# HANDS_FREE_MotorDrive_V2.net
KiCad netlist of a schematic drawn in Altium Designer
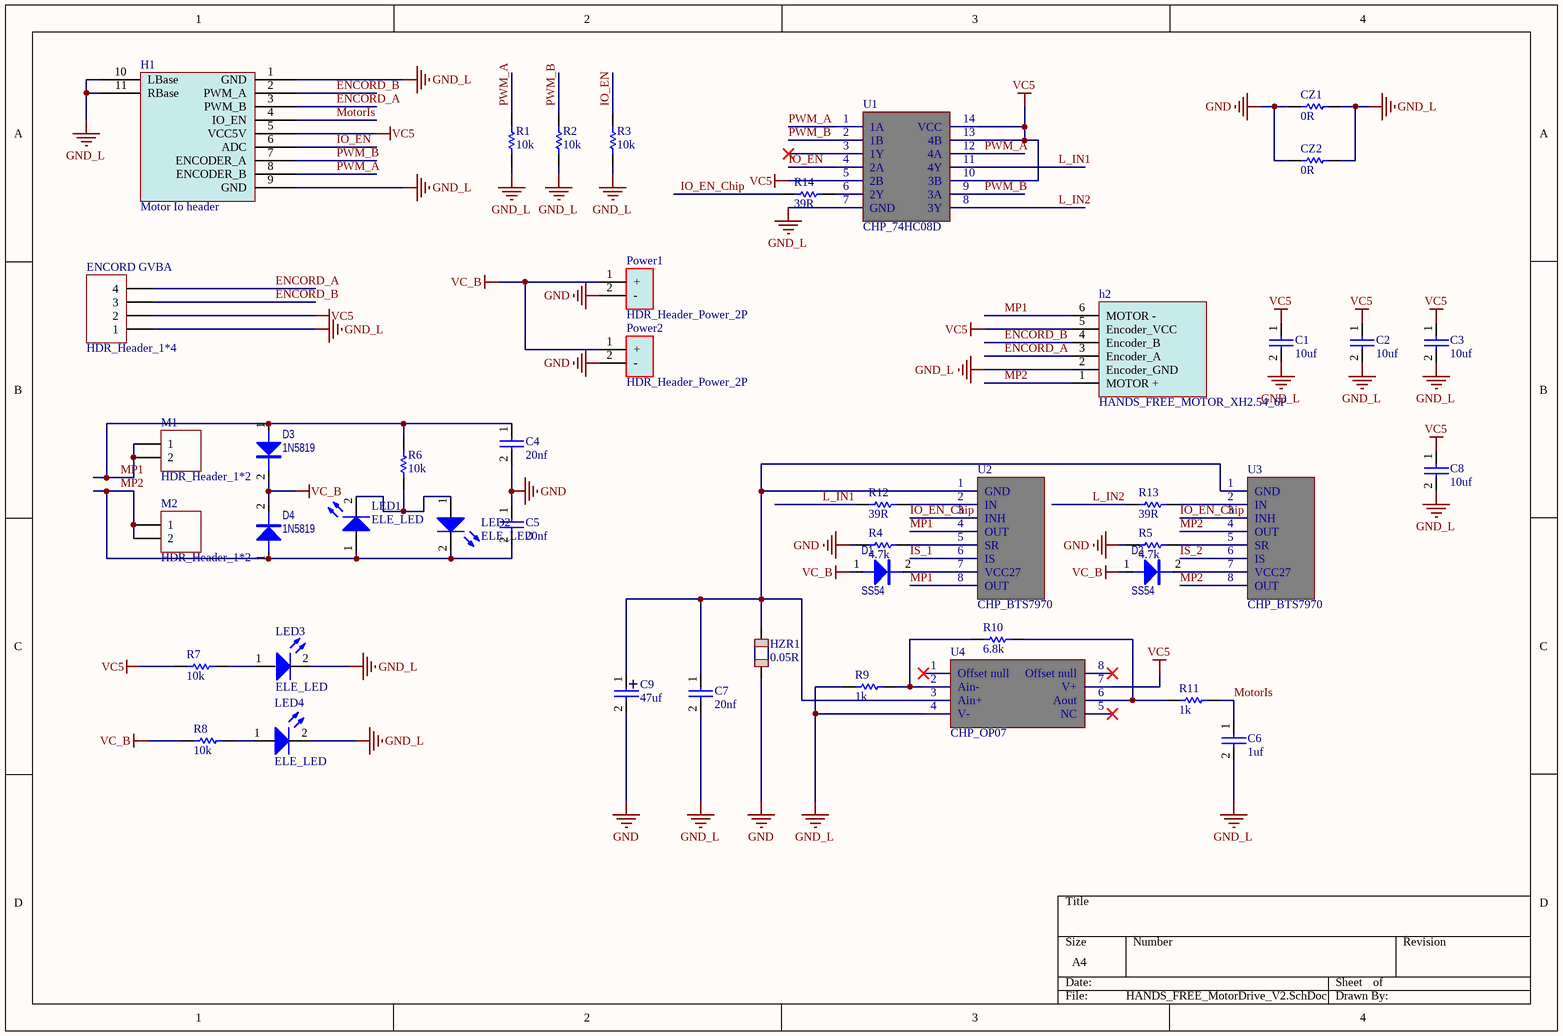
[diagram p0: HANDS_FREE_MotorDrive_V2.SchDoc]

(export (version "E")
  (design (tool "Eeschema 10.0.6"))
  (components
    (comp (ref "C1")
      (value "10uf")
      (footprint "ELE_0603_P")
      (description "电容")
      (libsource (lib "Hands_free") (part "ELE_Cap"))
    )
    (comp (ref "C2")
      (value "10uf")
      (footprint "ELE_0603_P")
      (description "电容")
      (libsource (lib "Hands_free") (part "ELE_Cap"))
    )
    (comp (ref "C3")
      (value "10uf")
      (footprint "ELE_0603_P")
      (description "电容")
      (libsource (lib "Hands_free") (part "ELE_Cap"))
    )
    (comp (ref "C4")
      (value "20nf")
      (footprint "ELE_0603_P")
      (description "电容")
      (libsource (lib "Hands_free") (part "ELE_Cap"))
    )
    (comp (ref "C5")
      (value "20nf")
      (footprint "ELE_0603_P")
      (description "电容")
      (libsource (lib "Hands_free") (part "ELE_Cap"))
    )
    (comp (ref "C6")
      (value "1uf")
      (footprint "ELE_0603_P")
      (description "电容")
      (libsource (lib "Hands_free") (part "ELE_Cap"))
    )
    (comp (ref "C7")
      (value "20nf")
      (footprint "ELE_0603_P")
      (description "电容")
      (libsource (lib "Hands_free") (part "ELE_Cap"))
    )
    (comp (ref "C8")
      (value "10uf")
      (footprint "ELE_0603_P")
      (description "电容")
      (libsource (lib "Hands_free") (part "ELE_Cap"))
    )
    (comp (ref "C9")
      (value "47uf")
      (footprint "ELE_CAP_DV_5*X")
      (description "贴片 极性电容 0603")
      (libsource (lib "Hands_free") (part "ELE_Cap_Pole"))
    )
    (comp (ref "CZ1")
      (value "0R")
      (footprint "ELE_0603_P")
      (description "贴片 电阻")
      (libsource (lib "Hands_free") (part "ELE_RES"))
    )
    (comp (ref "CZ2")
      (value "0R")
      (footprint "ELE_0603_P")
      (description "贴片 电阻")
      (libsource (lib "Hands_free") (part "ELE_RES"))
    )
    (comp (ref "D1")
      (value "SS54")
      (footprint "ELE_D1206")
      (description "贴片 二极管 1206")
      (libsource (lib "Hands_free") (part "ELE_Diode"))
    )
    (comp (ref "D2")
      (value "SS54")
      (footprint "ELE_D1206")
      (description "贴片 二极管 1206")
      (libsource (lib "Hands_free") (part "ELE_Diode"))
    )
    (comp (ref "D3")
      (value "1N5819")
      (footprint "ELE_SOD-323")
      (description "贴片 二极管 SOD323")
      (libsource (lib "Hands_free") (part "ELE_Standard_Diode_SOD323"))
    )
    (comp (ref "D4")
      (value "1N5819")
      (footprint "ELE_SOD-323")
      (description "贴片 二极管 SOD323")
      (libsource (lib "Hands_free") (part "ELE_Standard_Diode_SOD323"))
    )
    (comp (ref "ENCORD GVBA")
      (value "HDR_Header_1*4")
      (footprint "HDR_Header_2.54_PH_1*4")
      (fields (field (name "PUBLISHER") "Altium Limited"))
      (libsource (lib "Hands_free") (part "HDR_Header_1*4"))
    )
    (comp (ref "H1")
      (value "Motor Io header")
      (footprint "HDR_Molex_PH_1.25_9P")
      (description "卧贴 molex 1.25间距 9P接口")
      (libsource (lib "Hands_free") (part "HANDS_FREE_MOTOR"))
    )
    (comp (ref "h2")
      (value "HANDS_FREE_MOTOR_XH2.54_6P")
      (footprint "HDR_Header_XH2.54_DH_1*6")
      (description "直插 XH2.54 卧贴 6P")
      (libsource (lib "Hands_free") (part "HANDS_FREE_MOTOR_XH2.54_6P"))
    )
    (comp (ref "HZR1")
      (value "0.05R")
      (footprint "ELE_2512_P")
      (description "2512合金电阻 2W")
      (libsource (lib "Hands_free") (part "ELE_RES_HZR"))
    )
    (comp (ref "LED1")
      (value "ELE_LED")
      (footprint "ELE_0603极性_P")
      (description "发光二极管 0603")
      (fields (field (name "PUBLISHER") "Altium Limited"))
      (libsource (lib "Hands_free") (part "ELE_LED"))
    )
    (comp (ref "LED2")
      (value "ELE_LED")
      (footprint "ELE_0603极性_P")
      (description "发光二极管 0603")
      (fields (field (name "PUBLISHER") "Altium Limited"))
      (libsource (lib "Hands_free") (part "ELE_LED"))
    )
    (comp (ref "LED3")
      (value "ELE_LED")
      (footprint "ELE_0603极性_P")
      (description "发光二极管 0603")
      (fields (field (name "PUBLISHER") "Altium Limited"))
      (libsource (lib "Hands_free") (part "ELE_LED"))
    )
    (comp (ref "LED4")
      (value "ELE_LED")
      (footprint "ELE_0603极性_P")
      (description "发光二极管 0603")
      (fields (field (name "PUBLISHER") "Altium Limited"))
      (libsource (lib "Hands_free") (part "ELE_LED"))
    )
    (comp (ref "M1")
      (value "HDR_Header_1*2")
      (footprint "HDR_H_PH_2P")
      (fields (field (name "PUBLISHER") "Altium Limited"))
      (libsource (lib "Hands_free") (part "HDR_Header_1*2"))
    )
    (comp (ref "M2")
      (value "HDR_Header_1*2")
      (footprint "HDR_H_PH_2P")
      (fields (field (name "PUBLISHER") "Altium Limited"))
      (libsource (lib "Hands_free") (part "HDR_Header_1*2"))
    )
    (comp (ref "Power1")
      (value "HDR_Header_Power_2P")
      (footprint "HDR_MOLEX_POWER5557_DH_2P")
      (libsource (lib "Hands_free") (part "HDR_Header_Power_2P"))
    )
    (comp (ref "Power2")
      (value "HDR_Header_Power_2P")
      (footprint "HDR_MOLEX_POWER5557_DH_2P")
      (libsource (lib "Hands_free") (part "HDR_Header_Power_2P"))
    )
    (comp (ref "R1")
      (value "10k")
      (footprint "ELE_0603_P")
      (description "贴片 电阻")
      (libsource (lib "Hands_free") (part "ELE_RES"))
    )
    (comp (ref "R2")
      (value "10k")
      (footprint "ELE_0603_P")
      (description "贴片 电阻")
      (libsource (lib "Hands_free") (part "ELE_RES"))
    )
    (comp (ref "R3")
      (value "10k")
      (footprint "ELE_0603_P")
      (description "贴片 电阻")
      (libsource (lib "Hands_free") (part "ELE_RES"))
    )
    (comp (ref "R4")
      (value "4.7k")
      (footprint "ELE_0603_P")
      (description "贴片 电阻")
      (libsource (lib "Hands_free") (part "ELE_RES"))
    )
    (comp (ref "R5")
      (value "4.7k")
      (footprint "ELE_0603_P")
      (description "贴片 电阻")
      (libsource (lib "Hands_free") (part "ELE_RES"))
    )
    (comp (ref "R6")
      (value "10k")
      (footprint "ELE_0603_P")
      (description "贴片 电阻")
      (libsource (lib "Hands_free") (part "ELE_RES"))
    )
    (comp (ref "R7")
      (value "10k")
      (footprint "ELE_0603_P")
      (description "贴片 电阻")
      (libsource (lib "Hands_free") (part "ELE_RES"))
    )
    (comp (ref "R8")
      (value "10k")
      (footprint "ELE_0603_P")
      (description "贴片 电阻")
      (libsource (lib "Hands_free") (part "ELE_RES"))
    )
    (comp (ref "R9")
      (value "1k")
      (footprint "ELE_0603_P")
      (description "贴片 电阻")
      (libsource (lib "Hands_free") (part "ELE_RES"))
    )
    (comp (ref "R10")
      (value "6.8k")
      (footprint "ELE_0603_P")
      (description "贴片 电阻")
      (libsource (lib "Hands_free") (part "ELE_RES"))
    )
    (comp (ref "R11")
      (value "1k")
      (footprint "ELE_0603_P")
      (description "贴片 电阻")
      (libsource (lib "Hands_free") (part "ELE_RES"))
    )
    (comp (ref "R12")
      (value "39R")
      (footprint "ELE_0603_P")
      (description "贴片 电阻")
      (libsource (lib "Hands_free") (part "ELE_RES"))
    )
    (comp (ref "R13")
      (value "39R")
      (footprint "ELE_0603_P")
      (description "贴片 电阻")
      (libsource (lib "Hands_free") (part "ELE_RES"))
    )
    (comp (ref "R14")
      (value "39R")
      (footprint "ELE_0603_P")
      (description "贴片 电阻")
      (libsource (lib "Hands_free") (part "ELE_RES"))
    )
    (comp (ref "U1")
      (value "CHP_74HC08D")
      (footprint "CHP_SOP_14P")
      (description "贴片 CHP_74HC08D芯片 SOP_14P")
      (libsource (lib "Hands_free") (part "CHP_74HC08D"))
    )
    (comp (ref "U2")
      (value "CHP_BTS7970")
      (footprint "CHP_BTS7970_P-TO-263_7")
      (libsource (lib "Hands_free") (part "CHP_BTS7970"))
    )
    (comp (ref "U3")
      (value "CHP_BTS7970")
      (footprint "CHP_BTS7970_P-TO-263_7")
      (libsource (lib "Hands_free") (part "CHP_BTS7970"))
    )
    (comp (ref "U4")
      (value "CHP_OP07")
      (footprint "CHP_SOP_8P")
      (description "贴片 OP07芯片 SOP_8P")
      (libsource (lib "Hands_free") (part "CHP_OP07"))
    )
  )
  (nets
    (net (code "1") (name "/ENCORD_A") (class "Default")
      (node (ref "ENCORD GVBA") (pin "4") (pinfunction "4_4") (pintype "passive"))
      (node (ref "H1") (pin "3") (pinfunction "PWM_B_3") (pintype "passive"))
      (node (ref "h2") (pin "3") (pinfunction "Encoder_A_3") (pintype "passive"))
    )
    (net (code "2") (name "/ENCORD_B") (class "Default")
      (node (ref "ENCORD GVBA") (pin "3") (pinfunction "3_3") (pintype "passive"))
      (node (ref "H1") (pin "2") (pinfunction "PWM_A_2") (pintype "passive"))
      (node (ref "h2") (pin "4") (pinfunction "Encoder_B_4") (pintype "passive"))
    )
    (net (code "3") (name "/IO_EN") (class "Default")
      (node (ref "H1") (pin "6") (pinfunction "ADC_6") (pintype "passive"))
      (node (ref "R3") (pin "1") (pinfunction "1_1") (pintype "passive"))
      (node (ref "U1") (pin "4") (pinfunction "2A_4") (pintype "passive"))
    )
    (net (code "4") (name "/IO_EN_Chip") (class "Default")
      (node (ref "R14") (pin "1") (pinfunction "1_1") (pintype "passive"))
      (node (ref "U2") (pin "3") (pinfunction "INH_3") (pintype "passive"))
      (node (ref "U3") (pin "3") (pinfunction "INH_3") (pintype "passive"))
    )
    (net (code "5") (name "/IS_1") (class "Default")
      (node (ref "U2") (pin "6") (pinfunction "IS_6") (pintype "passive"))
    )
    (net (code "6") (name "/IS_2") (class "Default")
      (node (ref "U3") (pin "6") (pinfunction "IS_6") (pintype "passive"))
    )
    (net (code "7") (name "/L_IN1") (class "Default")
      (node (ref "R12") (pin "1") (pinfunction "1_1") (pintype "passive"))
      (node (ref "U1") (pin "11") (pinfunction "4Y_11") (pintype "passive"))
    )
    (net (code "8") (name "/L_IN2") (class "Default")
      (node (ref "R13") (pin "1") (pinfunction "1_1") (pintype "passive"))
      (node (ref "U1") (pin "8") (pinfunction "3Y_8") (pintype "passive"))
    )
    (net (code "9") (name "/MP1") (class "Default")
      (node (ref "C4") (pin "1") (pintype "passive"))
      (node (ref "D3") (pin "1") (pintype "passive"))
      (node (ref "M1") (pin "1") (pinfunction "1_1") (pintype "passive"))
      (node (ref "M1") (pin "2") (pinfunction "2_2") (pintype "passive"))
      (node (ref "R6") (pin "2") (pinfunction "2_2") (pintype "passive"))
      (node (ref "U2") (pin "4") (pinfunction "OUT_4") (pintype "passive"))
      (node (ref "U2") (pin "8") (pinfunction "OUT_8") (pintype "passive"))
      (node (ref "h2") (pin "6") (pinfunction "MOTOR_-_6") (pintype "passive"))
    )
    (net (code "10") (name "/MP2") (class "Default")
      (node (ref "C5") (pin "2") (pintype "passive"))
      (node (ref "D4") (pin "1") (pintype "passive"))
      (node (ref "LED1") (pin "1") (pintype "passive"))
      (node (ref "LED2") (pin "2") (pintype "passive"))
      (node (ref "M2") (pin "1") (pinfunction "1_1") (pintype "passive"))
      (node (ref "M2") (pin "2") (pinfunction "2_2") (pintype "passive"))
      (node (ref "U3") (pin "4") (pinfunction "OUT_4") (pintype "passive"))
      (node (ref "U3") (pin "8") (pinfunction "OUT_8") (pintype "passive"))
      (node (ref "h2") (pin "1") (pinfunction "MOTOR_+_1") (pintype "passive"))
    )
    (net (code "11") (name "/MotorIs") (class "Default")
      (node (ref "C6") (pin "1") (pintype "passive"))
      (node (ref "H1") (pin "4") (pinfunction "IO_EN_4") (pintype "passive"))
      (node (ref "R11") (pin "2") (pinfunction "2_2") (pintype "passive"))
    )
    (net (code "12") (name "/PWM_A") (class "Default")
      (node (ref "H1") (pin "8") (pinfunction "ENCODER_B_8") (pintype "passive"))
      (node (ref "R1") (pin "1") (pinfunction "1_1") (pintype "passive"))
      (node (ref "U1") (pin "1") (pinfunction "1A_1") (pintype "passive"))
      (node (ref "U1") (pin "12") (pinfunction "4A_12") (pintype "passive"))
    )
    (net (code "13") (name "/PWM_B") (class "Default")
      (node (ref "H1") (pin "7") (pinfunction "ENCODER_A_7") (pintype "passive"))
      (node (ref "R2") (pin "1") (pinfunction "1_1") (pintype "passive"))
      (node (ref "U1") (pin "2") (pinfunction "1B_2") (pintype "passive"))
      (node (ref "U1") (pin "9") (pinfunction "3A_9") (pintype "passive"))
    )
    (net (code "14") (name "GND") (class "Default")
      (node (ref "C4") (pin "2") (pintype "passive"))
      (node (ref "C5") (pin "1") (pintype "passive"))
      (node (ref "C9") (pin "2") (pintype "passive"))
      (node (ref "CZ1") (pin "1") (pinfunction "1_1") (pintype "passive"))
      (node (ref "CZ2") (pin "1") (pinfunction "1_1") (pintype "passive"))
      (node (ref "HZR1") (pin "2") (pinfunction "2_2") (pintype "passive"))
      (node (ref "Power1") (pin "2") (pinfunction "-_2") (pintype "passive"))
      (node (ref "Power2") (pin "2") (pinfunction "-_2") (pintype "passive"))
      (node (ref "R4") (pin "1") (pinfunction "1_1") (pintype "passive"))
      (node (ref "R5") (pin "1") (pinfunction "1_1") (pintype "passive"))
    )
    (net (code "15") (name "GND_L") (class "Default")
      (node (ref "C1") (pin "2") (pintype "passive"))
      (node (ref "C2") (pin "2") (pintype "passive"))
      (node (ref "C3") (pin "2") (pintype "passive"))
      (node (ref "C6") (pin "2") (pintype "passive"))
      (node (ref "C7") (pin "2") (pintype "passive"))
      (node (ref "C8") (pin "2") (pintype "passive"))
      (node (ref "CZ1") (pin "2") (pinfunction "2_2") (pintype "passive"))
      (node (ref "CZ2") (pin "2") (pinfunction "2_2") (pintype "passive"))
      (node (ref "ENCORD GVBA") (pin "1") (pinfunction "1_1") (pintype "passive"))
      (node (ref "H1") (pin "1") (pinfunction "GND_1") (pintype "passive"))
      (node (ref "H1") (pin "10") (pinfunction "LBase_10") (pintype "passive"))
      (node (ref "H1") (pin "11") (pinfunction "RBase_11") (pintype "passive"))
      (node (ref "H1") (pin "9") (pinfunction "GND_9") (pintype "passive"))
      (node (ref "LED3") (pin "2") (pintype "passive"))
      (node (ref "LED4") (pin "2") (pintype "passive"))
      (node (ref "R1") (pin "2") (pinfunction "2_2") (pintype "passive"))
      (node (ref "R2") (pin "2") (pinfunction "2_2") (pintype "passive"))
      (node (ref "R3") (pin "2") (pinfunction "2_2") (pintype "passive"))
      (node (ref "R9") (pin "1") (pinfunction "1_1") (pintype "passive"))
      (node (ref "U1") (pin "7") (pinfunction "GND_7") (pintype "passive"))
      (node (ref "U4") (pin "4") (pinfunction "V-_4") (pintype "passive"))
      (node (ref "h2") (pin "2") (pinfunction "Encoder_GND_2") (pintype "passive"))
    )
    (net (code "16") (name "Net-(LED1-Pad2)") (class "Default")
      (node (ref "LED1") (pin "2") (pintype "passive"))
      (node (ref "LED2") (pin "1") (pintype "passive"))
      (node (ref "R6") (pin "1") (pinfunction "1_1") (pintype "passive"))
    )
    (net (code "17") (name "Net-(LED3-Pad1)") (class "Default")
      (node (ref "LED3") (pin "1") (pintype "passive"))
      (node (ref "R7") (pin "1") (pinfunction "1_1") (pintype "passive"))
    )
    (net (code "18") (name "Net-(LED4-Pad1)") (class "Default")
      (node (ref "LED4") (pin "1") (pintype "passive"))
      (node (ref "R8") (pin "1") (pinfunction "1_1") (pintype "passive"))
    )
    (net (code "19") (name "Net-(U1-2Y)") (class "Default")
      (node (ref "R14") (pin "2") (pinfunction "2_2") (pintype "passive"))
      (node (ref "U1") (pin "6") (pinfunction "2Y_6") (pintype "passive"))
    )
    (net (code "20") (name "Net-(U2-GND)") (class "Default")
      (node (ref "C7") (pin "1") (pintype "passive"))
      (node (ref "C9") (pin "1") (pintype "passive"))
      (node (ref "HZR1") (pin "1") (pinfunction "1_1") (pintype "passive"))
      (node (ref "U2") (pin "1") (pinfunction "GND_1") (pintype "passive"))
      (node (ref "U3") (pin "1") (pinfunction "GND_1") (pintype "passive"))
      (node (ref "U4") (pin "3") (pinfunction "Ain+_3") (pintype "passive"))
    )
    (net (code "21") (name "Net-(U2-IN)") (class "Default")
      (node (ref "R12") (pin "2") (pinfunction "2_2") (pintype "passive"))
      (node (ref "U2") (pin "2") (pinfunction "IN_2") (pintype "passive"))
    )
    (net (code "22") (name "Net-(U2-SR)") (class "Default")
      (node (ref "R4") (pin "2") (pinfunction "2_2") (pintype "passive"))
      (node (ref "U2") (pin "5") (pinfunction "SR_5") (pintype "passive"))
    )
    (net (code "23") (name "Net-(U2-VCC27)") (class "Default")
      (node (ref "D1") (pin "2") (pintype "passive"))
      (node (ref "U2") (pin "7") (pinfunction "VCC27_7") (pintype "passive"))
    )
    (net (code "24") (name "Net-(U3-IN)") (class "Default")
      (node (ref "R13") (pin "2") (pinfunction "2_2") (pintype "passive"))
      (node (ref "U3") (pin "2") (pinfunction "IN_2") (pintype "passive"))
    )
    (net (code "25") (name "Net-(U3-SR)") (class "Default")
      (node (ref "R5") (pin "2") (pinfunction "2_2") (pintype "passive"))
      (node (ref "U3") (pin "5") (pinfunction "SR_5") (pintype "passive"))
    )
    (net (code "26") (name "Net-(U3-VCC27)") (class "Default")
      (node (ref "D2") (pin "2") (pintype "passive"))
      (node (ref "U3") (pin "7") (pinfunction "VCC27_7") (pintype "passive"))
    )
    (net (code "27") (name "Net-(U4-Ain-)") (class "Default")
      (node (ref "R10") (pin "1") (pinfunction "1_1") (pintype "passive"))
      (node (ref "R9") (pin "2") (pinfunction "2_2") (pintype "passive"))
      (node (ref "U4") (pin "2") (pinfunction "Ain-_2") (pintype "passive"))
    )
    (net (code "28") (name "Net-(U4-Aout)") (class "Default")
      (node (ref "R10") (pin "2") (pinfunction "2_2") (pintype "passive"))
      (node (ref "R11") (pin "1") (pinfunction "1_1") (pintype "passive"))
      (node (ref "U4") (pin "6") (pinfunction "Aout_6") (pintype "passive"))
    )
    (net (code "29") (name "VC5") (class "Default")
      (node (ref "C1") (pin "1") (pintype "passive"))
      (node (ref "C2") (pin "1") (pintype "passive"))
      (node (ref "C3") (pin "1") (pintype "passive"))
      (node (ref "C8") (pin "1") (pintype "passive"))
      (node (ref "ENCORD GVBA") (pin "2") (pinfunction "2_2") (pintype "passive"))
      (node (ref "H1") (pin "5") (pinfunction "VCC5V_5") (pintype "passive"))
      (node (ref "R7") (pin "2") (pinfunction "2_2") (pintype "passive"))
      (node (ref "U1") (pin "10") (pinfunction "3B_10") (pintype "passive"))
      (node (ref "U1") (pin "13") (pinfunction "4B_13") (pintype "passive"))
      (node (ref "U1") (pin "14") (pinfunction "VCC_14") (pintype "passive"))
      (node (ref "U1") (pin "5") (pinfunction "2B_5") (pintype "passive"))
      (node (ref "U4") (pin "7") (pinfunction "V+_7") (pintype "passive"))
      (node (ref "h2") (pin "5") (pinfunction "Encoder_VCC_5") (pintype "passive"))
    )
    (net (code "30") (name "VC_B") (class "Default")
      (node (ref "D1") (pin "1") (pintype "passive"))
      (node (ref "D2") (pin "1") (pintype "passive"))
      (node (ref "D3") (pin "2") (pintype "passive"))
      (node (ref "D4") (pin "2") (pintype "passive"))
      (node (ref "Power1") (pin "1") (pinfunction "+_1") (pintype "passive"))
      (node (ref "Power2") (pin "1") (pinfunction "+_1") (pintype "passive"))
      (node (ref "R8") (pin "2") (pinfunction "2_2") (pintype "passive"))
    )
    (net (code "31") (name "unconnected-(U1-1Y-Pad3)") (class "Default")
      (node (ref "U1") (pin "3") (pinfunction "1Y_3") (pintype "passive+no_connect"))
    )
    (net (code "32") (name "unconnected-(U4-NC-Pad5)") (class "Default")
      (node (ref "U4") (pin "5") (pinfunction "NC_5") (pintype "passive+no_connect"))
    )
    (net (code "33") (name "unconnected-(U4-Offset_null-Pad1)") (class "Default")
      (node (ref "U4") (pin "1") (pinfunction "Offset_null_1") (pintype "passive+no_connect"))
    )
    (net (code "34") (name "unconnected-(U4-Offset_null-Pad8)") (class "Default")
      (node (ref "U4") (pin "8") (pinfunction "Offset_null_8") (pintype "passive+no_connect"))
    )
  )
)
